# mini64se-F103-R6.net
KiCad netlist of a schematic drawn in EAGLE
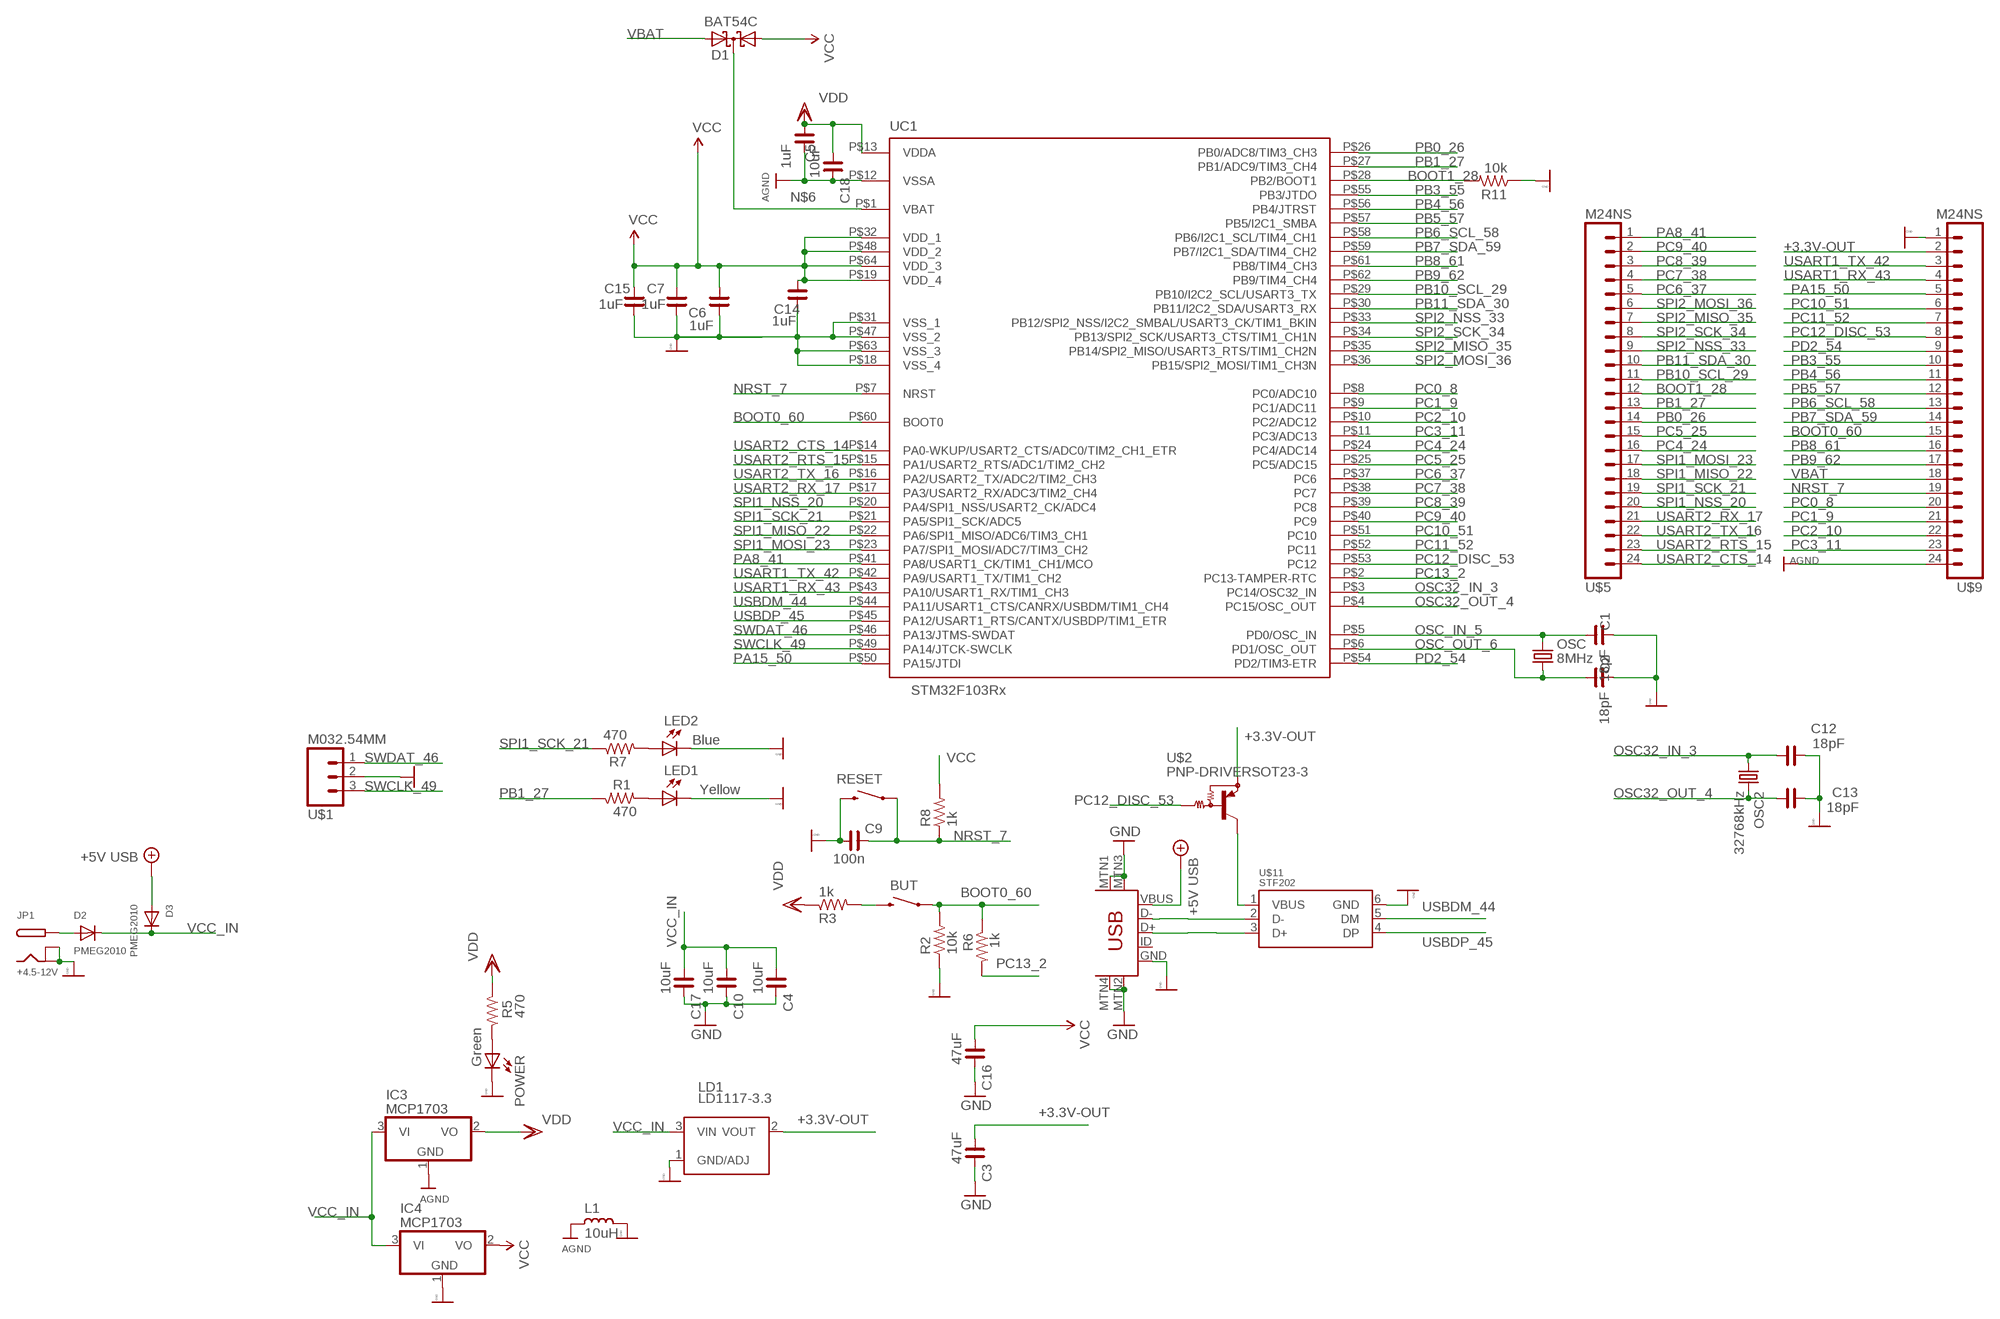
[diagram p0: schematic, sheet 1]

(export (version "E")
  (design (tool "Eeschema 10.0.6"))
  (components
    (comp (ref "BUT")
      (value "SWITCH-MOMENTARY-2-N59")
      (footprint "eagle-import:TACTILE-SWITCH-N59")
      (libsource (lib "eagle-import") (part "SWITCH-MOMENTARY-2-N59"))
    )
    (comp (ref "C1")
      (value "18pF")
      (footprint "eagle-import:C0603")
      (libsource (lib "eagle-import") (part "C_0603"))
    )
    (comp (ref "C2")
      (value "18pF")
      (footprint "eagle-import:C0603")
      (libsource (lib "eagle-import") (part "C_0603"))
    )
    (comp (ref "C3")
      (value "47uF")
      (footprint "eagle-import:C0805")
      (libsource (lib "eagle-import") (part "C_0805"))
    )
    (comp (ref "C4")
      (value "10uF")
      (footprint "eagle-import:C0603")
      (libsource (lib "eagle-import") (part "C_0603"))
    )
    (comp (ref "C5")
      (value "1uF")
      (footprint "eagle-import:C0603")
      (libsource (lib "eagle-import") (part "C_0603"))
    )
    (comp (ref "C6")
      (value "1uF")
      (footprint "eagle-import:C0603")
      (libsource (lib "eagle-import") (part "C_0603"))
    )
    (comp (ref "C7")
      (value "1uF")
      (footprint "eagle-import:C0603")
      (libsource (lib "eagle-import") (part "C_0603"))
    )
    (comp (ref "C9")
      (value "100n")
      (footprint "eagle-import:C0603")
      (libsource (lib "eagle-import") (part "C_0603"))
    )
    (comp (ref "C10")
      (value "10uF")
      (footprint "eagle-import:C0603")
      (libsource (lib "eagle-import") (part "C_0603"))
    )
    (comp (ref "C12")
      (value "18pF")
      (footprint "eagle-import:C0603")
      (libsource (lib "eagle-import") (part "C_0603"))
    )
    (comp (ref "C13")
      (value "18pF")
      (footprint "eagle-import:C0603")
      (libsource (lib "eagle-import") (part "C_0603"))
    )
    (comp (ref "C14")
      (value "1uF")
      (footprint "eagle-import:C0603")
      (libsource (lib "eagle-import") (part "C_0603"))
    )
    (comp (ref "C15")
      (value "1uF")
      (footprint "eagle-import:C0603")
      (libsource (lib "eagle-import") (part "C_0603"))
    )
    (comp (ref "C16")
      (value "47uF")
      (footprint "eagle-import:C0805")
      (libsource (lib "eagle-import") (part "C_0805"))
    )
    (comp (ref "C17")
      (value "10uF")
      (footprint "eagle-import:C0603")
      (libsource (lib "eagle-import") (part "C_0603"))
    )
    (comp (ref "C18")
      (value "10uF")
      (footprint "eagle-import:C0603")
      (libsource (lib "eagle-import") (part "C_0603"))
    )
    (comp (ref "D1")
      (value "BAT54C")
      (footprint "eagle-import:SOT23-3")
      (libsource (lib "eagle-import") (part "BAT54CRS"))
    )
    (comp (ref "D2")
      (value "PMEG2010")
      (footprint "eagle-import:SOD-323")
      (libsource (lib "eagle-import") (part "DIODESOD-323"))
    )
    (comp (ref "D3")
      (value "PMEG2010")
      (footprint "eagle-import:SOD-323")
      (libsource (lib "eagle-import") (part "DIODESOD-323"))
    )
    (comp (ref "IC3")
      (value "MCP1703")
      (footprint "eagle-import:SOT23-3")
      (libsource (lib "eagle-import") (part "MCP1703"))
    )
    (comp (ref "IC4")
      (value "MCP1703")
      (footprint "eagle-import:SOT23-3")
      (libsource (lib "eagle-import") (part "MCP1703"))
    )
    (comp (ref "JP1")
      (value "+4.5-12V")
      (footprint "eagle-import:DC-020-001")
      (libsource (lib "eagle-import") (part "DCJACK"))
    )
    (comp (ref "L1")
      (value "10uH")
      (footprint "eagle-import:L0603")
      (libsource (lib "eagle-import") (part "L_0603"))
    )
    (comp (ref "LD1")
      (value "LD1117-3.3")
      (footprint "eagle-import:SOT223")
      (libsource (lib "eagle-import") (part "LD1117SOT223"))
    )
    (comp (ref "LED1")
      (value "Yellow")
      (footprint "eagle-import:CHIP-LED0603")
      (libsource (lib "eagle-import") (part "LEDCHIP-LED0603"))
    )
    (comp (ref "LED2")
      (value "Blue")
      (footprint "eagle-import:CHIP-LED0603")
      (libsource (lib "eagle-import") (part "LEDCHIP-LED0603"))
    )
    (comp (ref "OSC")
      (value "8MHz")
      (footprint "eagle-import:HC49U-V")
      (libsource (lib "eagle-import") (part "CRYSTALHC49UV"))
    )
    (comp (ref "OSC2")
      (value "32768kHz")
      (footprint "eagle-import:TC26H-M")
      (libsource (lib "eagle-import") (part "CRYSTALTC26HM"))
    )
    (comp (ref "POWER")
      (value "Green")
      (footprint "eagle-import:CHIP-LED0603")
      (libsource (lib "eagle-import") (part "LEDCHIP-LED0603"))
    )
    (comp (ref "R1")
      (value "470")
      (footprint "eagle-import:R0603")
      (libsource (lib "eagle-import") (part "R_0603"))
    )
    (comp (ref "R2")
      (value "10k")
      (footprint "eagle-import:R0603")
      (libsource (lib "eagle-import") (part "R_0603"))
    )
    (comp (ref "R3")
      (value "1k")
      (footprint "eagle-import:R0603")
      (libsource (lib "eagle-import") (part "R_0603"))
    )
    (comp (ref "R5")
      (value "470")
      (footprint "eagle-import:R0603")
      (libsource (lib "eagle-import") (part "R_0603"))
    )
    (comp (ref "R6")
      (value "1k")
      (footprint "eagle-import:R0603")
      (libsource (lib "eagle-import") (part "R_0603"))
    )
    (comp (ref "R7")
      (value "470")
      (footprint "eagle-import:R0603")
      (libsource (lib "eagle-import") (part "R_0603"))
    )
    (comp (ref "R8")
      (value "1k")
      (footprint "eagle-import:R0603")
      (libsource (lib "eagle-import") (part "R_0603"))
    )
    (comp (ref "R11")
      (value "10k")
      (footprint "eagle-import:R0603")
      (libsource (lib "eagle-import") (part "R_0603"))
    )
    (comp (ref "RESET")
      (value "SWITCH-MOMENTARY-2-N59")
      (footprint "eagle-import:TACTILE-SWITCH-N59")
      (libsource (lib "eagle-import") (part "SWITCH-MOMENTARY-2-N59"))
    )
    (comp (ref "U$1")
      (value "M032.54MM")
      (footprint "eagle-import:1X03_NO_SILK")
      (libsource (lib "eagle-import") (part "M031X03_NO_SILK"))
    )
    (comp (ref "U$2")
      (value "PNP-DRIVERSOT23-3")
      (footprint "eagle-import:SOT23-3")
      (libsource (lib "eagle-import") (part "PNP-DRIVERSOT23-3"))
    )
    (comp (ref "U$5")
      (value "M24NS")
      (footprint "eagle-import:1X24_NO_SILK")
      (libsource (lib "eagle-import") (part "M24NS"))
    )
    (comp (ref "U$9")
      (value "M24NS")
      (footprint "eagle-import:1X24_NO_SILK")
      (libsource (lib "eagle-import") (part "M24NS"))
    )
    (comp (ref "U$11")
      (value "STF202")
      (footprint "eagle-import:TSOP-6")
      (libsource (lib "eagle-import") (part "STF202TSOP-6"))
    )
    (comp (ref "UC1")
      (value "STM32F103Rx")
      (footprint "eagle-import:TQFP-10X10-64")
      (libsource (lib "eagle-import") (part "STM32F103"))
    )
    (comp (ref "USB")
      (value "USB-MINIB-5PIN")
      (footprint "eagle-import:USB-MINIB")
      (libsource (lib "eagle-import") (part "USB-MINIB-5PIN"))
    )
  )
  (nets
    (net (code "1") (name "+5V USB") (class "Default")
      (node (ref "D3") (pin "A") (pinfunction "A_A") (pintype "passive"))
      (node (ref "USB") (pin "VBUS") (pinfunction "VBUS_VBUS") (pintype "bidirectional"))
    )
    (net (code "2") (name "/+3.3V-OUT") (class "Default")
      (node (ref "C3") (pin "1") (pinfunction "1_1") (pintype "passive"))
      (node (ref "LD1") (pin "2") (pinfunction "VOUT_2") (pintype "bidirectional"))
      (node (ref "U$2") (pin "2") (pinfunction "E_2") (pintype "passive"))
      (node (ref "U$9") (pin "2") (pinfunction "3_2") (pintype "passive"))
    )
    (net (code "3") (name "/BOOT0_60") (class "Default")
      (node (ref "BUT") (pin "P$1") (pinfunction "1_P$1") (pintype "passive"))
      (node (ref "R2") (pin "2") (pinfunction "2_2") (pintype "passive"))
      (node (ref "R6") (pin "1") (pinfunction "1_1") (pintype "passive"))
      (node (ref "U$9") (pin "15") (pinfunction "16_15") (pintype "passive"))
      (node (ref "UC1") (pin "P$60") (pinfunction "BOOT0_P$60") (pintype "bidirectional"))
    )
    (net (code "4") (name "/BOOT1_28") (class "Default")
      (node (ref "R11") (pin "2") (pinfunction "2_2") (pintype "passive"))
      (node (ref "U$5") (pin "12") (pinfunction "13_12") (pintype "passive"))
      (node (ref "UC1") (pin "P$28") (pinfunction "PB2/BOOT1_P$28") (pintype "bidirectional"))
    )
    (net (code "5") (name "/N$6") (class "Default")
      (node (ref "D1") (pin "3") (pinfunction "CC_3") (pintype "passive"))
      (node (ref "UC1") (pin "P$1") (pinfunction "VBAT_P$1") (pintype "power_in"))
    )
    (net (code "6") (name "/NRST_7") (class "Default")
      (node (ref "C9") (pin "2") (pinfunction "2_2") (pintype "passive"))
      (node (ref "R8") (pin "1") (pinfunction "1_1") (pintype "passive"))
      (node (ref "RESET") (pin "P$1") (pinfunction "1_P$1") (pintype "passive"))
      (node (ref "U$9") (pin "19") (pinfunction "20_19") (pintype "passive"))
      (node (ref "UC1") (pin "P$7") (pinfunction "NRST_P$7") (pintype "bidirectional"))
    )
    (net (code "7") (name "/OSC32_IN_3") (class "Default")
      (node (ref "C12") (pin "2") (pinfunction "2_2") (pintype "passive"))
      (node (ref "OSC2") (pin "1") (pinfunction "1_1") (pintype "passive"))
      (node (ref "UC1") (pin "P$3") (pinfunction "PC14/OSC32_IN_P$3") (pintype "bidirectional"))
    )
    (net (code "8") (name "/OSC32_OUT_4") (class "Default")
      (node (ref "C13") (pin "2") (pinfunction "2_2") (pintype "passive"))
      (node (ref "OSC2") (pin "2") (pinfunction "2_2") (pintype "passive"))
      (node (ref "UC1") (pin "P$4") (pinfunction "PC15/OSC_OUT_P$4") (pintype "bidirectional"))
    )
    (net (code "9") (name "/OSC_IN_5") (class "Default")
      (node (ref "C1") (pin "2") (pinfunction "2_2") (pintype "passive"))
      (node (ref "OSC") (pin "2") (pinfunction "2_2") (pintype "passive"))
      (node (ref "UC1") (pin "P$5") (pinfunction "PD0/OSC_IN_P$5") (pintype "bidirectional"))
    )
    (net (code "10") (name "/OSC_OUT_6") (class "Default")
      (node (ref "C2") (pin "2") (pinfunction "2_2") (pintype "passive"))
      (node (ref "OSC") (pin "1") (pinfunction "1_1") (pintype "passive"))
      (node (ref "UC1") (pin "P$6") (pinfunction "PD1/OSC_OUT_P$6") (pintype "bidirectional"))
    )
    (net (code "11") (name "/PA8_41") (class "Default")
      (node (ref "U$5") (pin "1") (pinfunction "2_1") (pintype "passive"))
      (node (ref "UC1") (pin "P$41") (pinfunction "PA8/USART1_CK/TIM1_CH1/MCO_P$41") (pintype "bidirectional"))
    )
    (net (code "12") (name "/PA15_50") (class "Default")
      (node (ref "U$9") (pin "5") (pinfunction "6_5") (pintype "passive"))
      (node (ref "UC1") (pin "P$50") (pinfunction "PA15/JTDI_P$50") (pintype "bidirectional"))
    )
    (net (code "13") (name "/PB0_26") (class "Default")
      (node (ref "U$5") (pin "14") (pinfunction "15_14") (pintype "passive"))
      (node (ref "UC1") (pin "P$26") (pinfunction "PB0/ADC8/TIM3_CH3_P$26") (pintype "bidirectional"))
    )
    (net (code "14") (name "/PB1_27") (class "Default")
      (node (ref "R1") (pin "2") (pinfunction "2_2") (pintype "passive"))
      (node (ref "U$5") (pin "13") (pinfunction "14_13") (pintype "passive"))
      (node (ref "UC1") (pin "P$27") (pinfunction "PB1/ADC9/TIM3_CH4_P$27") (pintype "bidirectional"))
    )
    (net (code "15") (name "/PB3_55") (class "Default")
      (node (ref "U$9") (pin "10") (pinfunction "11_10") (pintype "passive"))
      (node (ref "UC1") (pin "P$55") (pinfunction "PB3/JTDO_P$55") (pintype "bidirectional"))
    )
    (net (code "16") (name "/PB4_56") (class "Default")
      (node (ref "U$9") (pin "11") (pinfunction "12_11") (pintype "passive"))
      (node (ref "UC1") (pin "P$56") (pinfunction "PB4/JTRST_P$56") (pintype "bidirectional"))
    )
    (net (code "17") (name "/PB5_57") (class "Default")
      (node (ref "U$9") (pin "12") (pinfunction "13_12") (pintype "passive"))
      (node (ref "UC1") (pin "P$57") (pinfunction "PB5/I2C1_SMBA_P$57") (pintype "bidirectional"))
    )
    (net (code "18") (name "/PB6_SCL_58") (class "Default")
      (node (ref "U$9") (pin "13") (pinfunction "14_13") (pintype "passive"))
      (node (ref "UC1") (pin "P$58") (pinfunction "PB6/I2C1_SCL/TIM4_CH1_P$58") (pintype "bidirectional"))
    )
    (net (code "19") (name "/PB7_SDA_59") (class "Default")
      (node (ref "U$9") (pin "14") (pinfunction "15_14") (pintype "passive"))
      (node (ref "UC1") (pin "P$59") (pinfunction "PB7/I2C1_SDA/TIM4_CH2_P$59") (pintype "bidirectional"))
    )
    (net (code "20") (name "/PB8_61") (class "Default")
      (node (ref "U$9") (pin "16") (pinfunction "17_16") (pintype "passive"))
      (node (ref "UC1") (pin "P$61") (pinfunction "PB8/TIM4_CH3_P$61") (pintype "bidirectional"))
    )
    (net (code "21") (name "/PB9_62") (class "Default")
      (node (ref "U$9") (pin "17") (pinfunction "18_17") (pintype "passive"))
      (node (ref "UC1") (pin "P$62") (pinfunction "PB9/TIM4_CH4_P$62") (pintype "bidirectional"))
    )
    (net (code "22") (name "/PB10_SCL_29") (class "Default")
      (node (ref "U$5") (pin "11") (pinfunction "12_11") (pintype "passive"))
      (node (ref "UC1") (pin "P$29") (pinfunction "PB10/I2C2_SCL/USART3_TX_P$29") (pintype "bidirectional"))
    )
    (net (code "23") (name "/PB11_SDA_30") (class "Default")
      (node (ref "U$5") (pin "10") (pinfunction "11_10") (pintype "passive"))
      (node (ref "UC1") (pin "P$30") (pinfunction "PB11/I2C2_SDA/USART3_RX_P$30") (pintype "bidirectional"))
    )
    (net (code "24") (name "/PC0_8") (class "Default")
      (node (ref "U$9") (pin "20") (pinfunction "21_20") (pintype "passive"))
      (node (ref "UC1") (pin "P$8") (pinfunction "PC0/ADC10_P$8") (pintype "bidirectional"))
    )
    (net (code "25") (name "/PC1_9") (class "Default")
      (node (ref "U$9") (pin "21") (pinfunction "22_21") (pintype "passive"))
      (node (ref "UC1") (pin "P$9") (pinfunction "PC1/ADC11_P$9") (pintype "bidirectional"))
    )
    (net (code "26") (name "/PC2_10") (class "Default")
      (node (ref "U$9") (pin "22") (pinfunction "23_22") (pintype "passive"))
      (node (ref "UC1") (pin "P$10") (pinfunction "PC2/ADC12_P$10") (pintype "bidirectional"))
    )
    (net (code "27") (name "/PC3_11") (class "Default")
      (node (ref "U$9") (pin "23") (pinfunction "24_23") (pintype "passive"))
      (node (ref "UC1") (pin "P$11") (pinfunction "PC3/ADC13_P$11") (pintype "bidirectional"))
    )
    (net (code "28") (name "/PC4_24") (class "Default")
      (node (ref "U$5") (pin "16") (pinfunction "17_16") (pintype "passive"))
      (node (ref "UC1") (pin "P$24") (pinfunction "PC4/ADC14_P$24") (pintype "bidirectional"))
    )
    (net (code "29") (name "/PC5_25") (class "Default")
      (node (ref "U$5") (pin "15") (pinfunction "16_15") (pintype "passive"))
      (node (ref "UC1") (pin "P$25") (pinfunction "PC5/ADC15_P$25") (pintype "bidirectional"))
    )
    (net (code "30") (name "/PC6_37") (class "Default")
      (node (ref "U$5") (pin "5") (pinfunction "6_5") (pintype "passive"))
      (node (ref "UC1") (pin "P$37") (pinfunction "PC6_P$37") (pintype "bidirectional"))
    )
    (net (code "31") (name "/PC7_38") (class "Default")
      (node (ref "U$5") (pin "4") (pinfunction "5_4") (pintype "passive"))
      (node (ref "UC1") (pin "P$38") (pinfunction "PC7_P$38") (pintype "bidirectional"))
    )
    (net (code "32") (name "/PC8_39") (class "Default")
      (node (ref "U$5") (pin "3") (pinfunction "4_3") (pintype "passive"))
      (node (ref "UC1") (pin "P$39") (pinfunction "PC8_P$39") (pintype "bidirectional"))
    )
    (net (code "33") (name "/PC9_40") (class "Default")
      (node (ref "U$5") (pin "2") (pinfunction "3_2") (pintype "passive"))
      (node (ref "UC1") (pin "P$40") (pinfunction "PC9_P$40") (pintype "bidirectional"))
    )
    (net (code "34") (name "/PC10_51") (class "Default")
      (node (ref "U$9") (pin "6") (pinfunction "7_6") (pintype "passive"))
      (node (ref "UC1") (pin "P$51") (pinfunction "PC10_P$51") (pintype "bidirectional"))
    )
    (net (code "35") (name "/PC11_52") (class "Default")
      (node (ref "U$9") (pin "7") (pinfunction "8_7") (pintype "passive"))
      (node (ref "UC1") (pin "P$52") (pinfunction "PC11_P$52") (pintype "bidirectional"))
    )
    (net (code "36") (name "/PC12_DISC_53") (class "Default")
      (node (ref "U$2") (pin "1") (pinfunction "B_1") (pintype "passive"))
      (node (ref "U$9") (pin "8") (pinfunction "9_8") (pintype "passive"))
      (node (ref "UC1") (pin "P$53") (pinfunction "PC12_P$53") (pintype "bidirectional"))
    )
    (net (code "37") (name "/PC13_2") (class "Default")
      (node (ref "R6") (pin "2") (pinfunction "2_2") (pintype "passive"))
      (node (ref "UC1") (pin "P$2") (pinfunction "PC13-TAMPER-RTC_P$2") (pintype "bidirectional"))
    )
    (net (code "38") (name "/PD2_54") (class "Default")
      (node (ref "U$9") (pin "9") (pinfunction "10_9") (pintype "passive"))
      (node (ref "UC1") (pin "P$54") (pinfunction "PD2/TIM3-ETR_P$54") (pintype "bidirectional"))
    )
    (net (code "39") (name "/SPI1_MISO_22") (class "Default")
      (node (ref "U$5") (pin "18") (pinfunction "19_18") (pintype "passive"))
      (node (ref "UC1") (pin "P$22") (pinfunction "PA6/SPI1_MISO/ADC6/TIM3_CH1_P$22") (pintype "bidirectional"))
    )
    (net (code "40") (name "/SPI1_MOSI_23") (class "Default")
      (node (ref "U$5") (pin "17") (pinfunction "18_17") (pintype "passive"))
      (node (ref "UC1") (pin "P$23") (pinfunction "PA7/SPI1_MOSI/ADC7/TIM3_CH2_P$23") (pintype "bidirectional"))
    )
    (net (code "41") (name "/SPI1_NSS_20") (class "Default")
      (node (ref "U$5") (pin "20") (pinfunction "21_20") (pintype "passive"))
      (node (ref "UC1") (pin "P$20") (pinfunction "PA4/SPI1_NSS/USART2_CK/ADC4_P$20") (pintype "bidirectional"))
    )
    (net (code "42") (name "/SPI1_SCK_21") (class "Default")
      (node (ref "R7") (pin "1") (pinfunction "1_1") (pintype "passive"))
      (node (ref "U$5") (pin "19") (pinfunction "20_19") (pintype "passive"))
      (node (ref "UC1") (pin "P$21") (pinfunction "PA5/SPI1_SCK/ADC5_P$21") (pintype "bidirectional"))
    )
    (net (code "43") (name "/SPI2_MISO_35") (class "Default")
      (node (ref "U$5") (pin "7") (pinfunction "8_7") (pintype "passive"))
      (node (ref "UC1") (pin "P$35") (pinfunction "PB14/SPI2_MISO/USART3_RTS/TIM1_CH2N_P$35") (pintype "bidirectional"))
    )
    (net (code "44") (name "/SPI2_MOSI_36") (class "Default")
      (node (ref "U$5") (pin "6") (pinfunction "7_6") (pintype "passive"))
      (node (ref "UC1") (pin "P$36") (pinfunction "PB15/SPI2_MOSI/TIM1_CH3N_P$36") (pintype "bidirectional"))
    )
    (net (code "45") (name "/SPI2_NSS_33") (class "Default")
      (node (ref "U$5") (pin "9") (pinfunction "10_9") (pintype "passive"))
      (node (ref "UC1") (pin "P$33") (pinfunction "PB12/SPI2_NSS/I2C2_SMBAL/USART3_CK/TIM1_BKIN_P$33") (pintype "bidirectional"))
    )
    (net (code "46") (name "/SPI2_SCK_34") (class "Default")
      (node (ref "U$5") (pin "8") (pinfunction "9_8") (pintype "passive"))
      (node (ref "UC1") (pin "P$34") (pinfunction "PB13/SPI2_SCK/USART3_CTS/TIM1_CH1N_P$34") (pintype "bidirectional"))
    )
    (net (code "47") (name "/SWCLK_49") (class "Default")
      (node (ref "U$1") (pin "3") (pinfunction "3_3") (pintype "passive"))
      (node (ref "UC1") (pin "P$49") (pinfunction "PA14/JTCK-SWCLK_P$49") (pintype "bidirectional"))
    )
    (net (code "48") (name "/SWDAT_46") (class "Default")
      (node (ref "U$1") (pin "1") (pinfunction "1_1") (pintype "passive"))
      (node (ref "UC1") (pin "P$46") (pinfunction "PA13/JTMS-SWDAT_P$46") (pintype "bidirectional"))
    )
    (net (code "49") (name "/USART1_RX_43") (class "Default")
      (node (ref "U$9") (pin "4") (pinfunction "5_4") (pintype "passive"))
      (node (ref "UC1") (pin "P$43") (pinfunction "PA10/USART1_RX/TIM1_CH3_P$43") (pintype "bidirectional"))
    )
    (net (code "50") (name "/USART1_TX_42") (class "Default")
      (node (ref "U$9") (pin "3") (pinfunction "4_3") (pintype "passive"))
      (node (ref "UC1") (pin "P$42") (pinfunction "PA9/USART1_TX/TIM1_CH2_P$42") (pintype "bidirectional"))
    )
    (net (code "51") (name "/USART2_CTS_14") (class "Default")
      (node (ref "U$5") (pin "24") (pinfunction "25_24") (pintype "passive"))
      (node (ref "UC1") (pin "P$14") (pinfunction "PA0-WKUP/USART2_CTS/ADC0/TIM2_CH1_ETR_P$14") (pintype "bidirectional"))
    )
    (net (code "52") (name "/USART2_RTS_15") (class "Default")
      (node (ref "U$5") (pin "23") (pinfunction "24_23") (pintype "passive"))
      (node (ref "UC1") (pin "P$15") (pinfunction "PA1/USART2_RTS/ADC1/TIM2_CH2_P$15") (pintype "bidirectional"))
    )
    (net (code "53") (name "/USART2_RX_17") (class "Default")
      (node (ref "U$5") (pin "21") (pinfunction "22_21") (pintype "passive"))
      (node (ref "UC1") (pin "P$17") (pinfunction "PA3/USART2_RX/ADC3/TIM2_CH4_P$17") (pintype "bidirectional"))
    )
    (net (code "54") (name "/USART2_TX_16") (class "Default")
      (node (ref "U$5") (pin "22") (pinfunction "23_22") (pintype "passive"))
      (node (ref "UC1") (pin "P$16") (pinfunction "PA2/USART2_TX/ADC2/TIM2_CH3_P$16") (pintype "bidirectional"))
    )
    (net (code "55") (name "/USBDM_44") (class "Default")
      (node (ref "U$11") (pin "5") (pinfunction "DM_5") (pintype "bidirectional"))
      (node (ref "UC1") (pin "P$44") (pinfunction "PA11/USART1_CTS/CANRX/USBDM/TIM1_CH4_P$44") (pintype "bidirectional"))
    )
    (net (code "56") (name "/USBDP_45") (class "Default")
      (node (ref "U$11") (pin "4") (pinfunction "DP_4") (pintype "bidirectional"))
      (node (ref "UC1") (pin "P$45") (pinfunction "PA12/USART1_RTS/CANTX/USBDP/TIM1_ETR_P$45") (pintype "bidirectional"))
    )
    (net (code "57") (name "/VBAT") (class "Default")
      (node (ref "D1") (pin "2") (pinfunction "A2_2") (pintype "passive"))
      (node (ref "U$9") (pin "18") (pinfunction "19_18") (pintype "passive"))
    )
    (net (code "58") (name "/VCC_IN") (class "Default")
      (node (ref "C10") (pin "1") (pinfunction "1_1") (pintype "passive"))
      (node (ref "C17") (pin "1") (pinfunction "1_1") (pintype "passive"))
      (node (ref "C4") (pin "1") (pinfunction "1_1") (pintype "passive"))
      (node (ref "D2") (pin "C") (pinfunction "C_C") (pintype "passive"))
      (node (ref "D3") (pin "C") (pinfunction "C_C") (pintype "passive"))
      (node (ref "IC3") (pin "3") (pinfunction "VI_3") (pintype "input"))
      (node (ref "IC4") (pin "3") (pinfunction "VI_3") (pintype "input"))
      (node (ref "LD1") (pin "3") (pinfunction "VIN_3") (pintype "bidirectional"))
    )
    (net (code "59") (name "AGND") (class "Default")
      (node (ref "C18") (pin "2") (pinfunction "2_2") (pintype "passive"))
      (node (ref "C5") (pin "1") (pinfunction "1_1") (pintype "passive"))
      (node (ref "IC3") (pin "1") (pinfunction "GND_1") (pintype "passive"))
      (node (ref "L1") (pin "2") (pinfunction "2_2") (pintype "passive"))
      (node (ref "U$9") (pin "24") (pinfunction "25_24") (pintype "passive"))
      (node (ref "UC1") (pin "P$12") (pinfunction "VSSA_P$12") (pintype "power_in"))
    )
    (net (code "60") (name "GND") (class "Default")
      (node (ref "C1") (pin "1") (pinfunction "1_1") (pintype "passive"))
      (node (ref "C10") (pin "2") (pinfunction "2_2") (pintype "passive"))
      (node (ref "C12") (pin "1") (pinfunction "1_1") (pintype "passive"))
      (node (ref "C13") (pin "1") (pinfunction "1_1") (pintype "passive"))
      (node (ref "C14") (pin "1") (pinfunction "1_1") (pintype "passive"))
      (node (ref "C15") (pin "1") (pinfunction "1_1") (pintype "passive"))
      (node (ref "C16") (pin "2") (pinfunction "2_2") (pintype "passive"))
      (node (ref "C17") (pin "2") (pinfunction "2_2") (pintype "passive"))
      (node (ref "C2") (pin "1") (pinfunction "1_1") (pintype "passive"))
      (node (ref "C3") (pin "2") (pinfunction "2_2") (pintype "passive"))
      (node (ref "C4") (pin "2") (pinfunction "2_2") (pintype "passive"))
      (node (ref "C6") (pin "1") (pinfunction "1_1") (pintype "passive"))
      (node (ref "C7") (pin "1") (pinfunction "1_1") (pintype "passive"))
      (node (ref "C9") (pin "1") (pinfunction "1_1") (pintype "passive"))
      (node (ref "IC4") (pin "1") (pinfunction "GND_1") (pintype "passive"))
      (node (ref "JP1") (pin "GND") (pinfunction "GND_GND") (pintype "power_in"))
      (node (ref "JP1") (pin "GNDBREAK") (pinfunction "GNDBREAK_GNDBREAK") (pintype "power_in"))
      (node (ref "L1") (pin "1") (pinfunction "1_1") (pintype "passive"))
      (node (ref "LD1") (pin "1") (pinfunction "GND/ADJ_1") (pintype "bidirectional"))
      (node (ref "LED1") (pin "C") (pinfunction "C_C") (pintype "passive"))
      (node (ref "LED2") (pin "C") (pinfunction "C_C") (pintype "passive"))
      (node (ref "POWER") (pin "C") (pinfunction "C_C") (pintype "passive"))
      (node (ref "R11") (pin "1") (pinfunction "1_1") (pintype "passive"))
      (node (ref "R2") (pin "1") (pinfunction "1_1") (pintype "passive"))
      (node (ref "RESET") (pin "P$2") (pinfunction "2_P$2") (pintype "passive"))
      (node (ref "U$1") (pin "2") (pinfunction "2_2") (pintype "passive"))
      (node (ref "U$11") (pin "6") (pinfunction "GND_6") (pintype "bidirectional"))
      (node (ref "U$9") (pin "1") (pinfunction "2_1") (pintype "passive"))
      (node (ref "UC1") (pin "P$18") (pinfunction "VSS_4_P$18") (pintype "power_in"))
      (node (ref "UC1") (pin "P$31") (pinfunction "VSS_1_P$31") (pintype "power_in"))
      (node (ref "UC1") (pin "P$47") (pinfunction "VSS_2_P$47") (pintype "power_in"))
      (node (ref "UC1") (pin "P$63") (pinfunction "VSS_3_P$63") (pintype "power_in"))
      (node (ref "USB") (pin "GND") (pinfunction "GND_GND") (pintype "bidirectional"))
      (node (ref "USB") (pin "MTN1") (pinfunction "MTN2_MTN1") (pintype "bidirectional"))
      (node (ref "USB") (pin "MTN2") (pinfunction "MTN3_MTN2") (pintype "bidirectional"))
      (node (ref "USB") (pin "MTN3") (pinfunction "MTN1_MTN3") (pintype "bidirectional"))
      (node (ref "USB") (pin "MTN4") (pinfunction "MTN4_MTN4") (pintype "bidirectional"))
    )
    (net (code "61") (name "Net-(BUT-2)") (class "Default")
      (node (ref "BUT") (pin "P$2") (pinfunction "2_P$2") (pintype "passive"))
      (node (ref "R3") (pin "2") (pinfunction "2_2") (pintype "passive"))
    )
    (net (code "62") (name "Net-(D2-PadA)") (class "Default")
      (node (ref "D2") (pin "A") (pinfunction "A_A") (pintype "passive"))
      (node (ref "JP1") (pin "PWR") (pinfunction "PWR_PWR") (pintype "power_in"))
    )
    (net (code "63") (name "Net-(LED1-PadA)") (class "Default")
      (node (ref "LED1") (pin "A") (pinfunction "A_A") (pintype "passive"))
      (node (ref "R1") (pin "1") (pinfunction "1_1") (pintype "passive"))
    )
    (net (code "64") (name "Net-(LED2-PadA)") (class "Default")
      (node (ref "LED2") (pin "A") (pinfunction "A_A") (pintype "passive"))
      (node (ref "R7") (pin "2") (pinfunction "2_2") (pintype "passive"))
    )
    (net (code "65") (name "Net-(POWER-PadA)") (class "Default")
      (node (ref "POWER") (pin "A") (pinfunction "A_A") (pintype "passive"))
      (node (ref "R5") (pin "2") (pinfunction "2_2") (pintype "passive"))
    )
    (net (code "66") (name "Net-(U$11-D+)") (class "Default")
      (node (ref "U$11") (pin "3") (pinfunction "D+_3") (pintype "bidirectional"))
      (node (ref "USB") (pin "D+") (pinfunction "D+_D+") (pintype "bidirectional"))
    )
    (net (code "67") (name "Net-(U$11-D-)") (class "Default")
      (node (ref "U$11") (pin "2") (pinfunction "D-_2") (pintype "bidirectional"))
      (node (ref "USB") (pin "D-") (pinfunction "D-_D-") (pintype "bidirectional"))
    )
    (net (code "68") (name "Net-(U$11-VBUS)") (class "Default")
      (node (ref "U$11") (pin "1") (pinfunction "VBUS_1") (pintype "bidirectional"))
      (node (ref "U$2") (pin "3") (pinfunction "C_3") (pintype "passive"))
    )
    (net (code "69") (name "VCC") (class "Default")
      (node (ref "C14") (pin "2") (pinfunction "2_2") (pintype "passive"))
      (node (ref "C15") (pin "2") (pinfunction "2_2") (pintype "passive"))
      (node (ref "C16") (pin "1") (pinfunction "1_1") (pintype "passive"))
      (node (ref "C6") (pin "2") (pinfunction "2_2") (pintype "passive"))
      (node (ref "C7") (pin "2") (pinfunction "2_2") (pintype "passive"))
      (node (ref "D1") (pin "1") (pinfunction "A1_1") (pintype "passive"))
      (node (ref "IC4") (pin "2") (pinfunction "VO_2") (pintype "passive"))
      (node (ref "R8") (pin "2") (pinfunction "2_2") (pintype "passive"))
      (node (ref "UC1") (pin "P$19") (pinfunction "VDD_4_P$19") (pintype "power_in"))
      (node (ref "UC1") (pin "P$32") (pinfunction "VDD_1_P$32") (pintype "power_in"))
      (node (ref "UC1") (pin "P$48") (pinfunction "VDD_2_P$48") (pintype "power_in"))
      (node (ref "UC1") (pin "P$64") (pinfunction "VDD_3_P$64") (pintype "power_in"))
    )
    (net (code "70") (name "VDD") (class "Default")
      (node (ref "C18") (pin "1") (pinfunction "1_1") (pintype "passive"))
      (node (ref "C5") (pin "2") (pinfunction "2_2") (pintype "passive"))
      (node (ref "IC3") (pin "2") (pinfunction "VO_2") (pintype "passive"))
      (node (ref "R3") (pin "1") (pinfunction "1_1") (pintype "passive"))
      (node (ref "R5") (pin "1") (pinfunction "1_1") (pintype "passive"))
      (node (ref "UC1") (pin "P$13") (pinfunction "VDDA_P$13") (pintype "power_in"))
    )
    (net (code "71") (name "unconnected-(USB-PadID)") (class "Default")
      (node (ref "USB") (pin "ID") (pinfunction "ID_ID") (pintype "bidirectional"))
    )
  )
)
